# design.net
KiCad netlist of a schematic drawn in Altium Designer
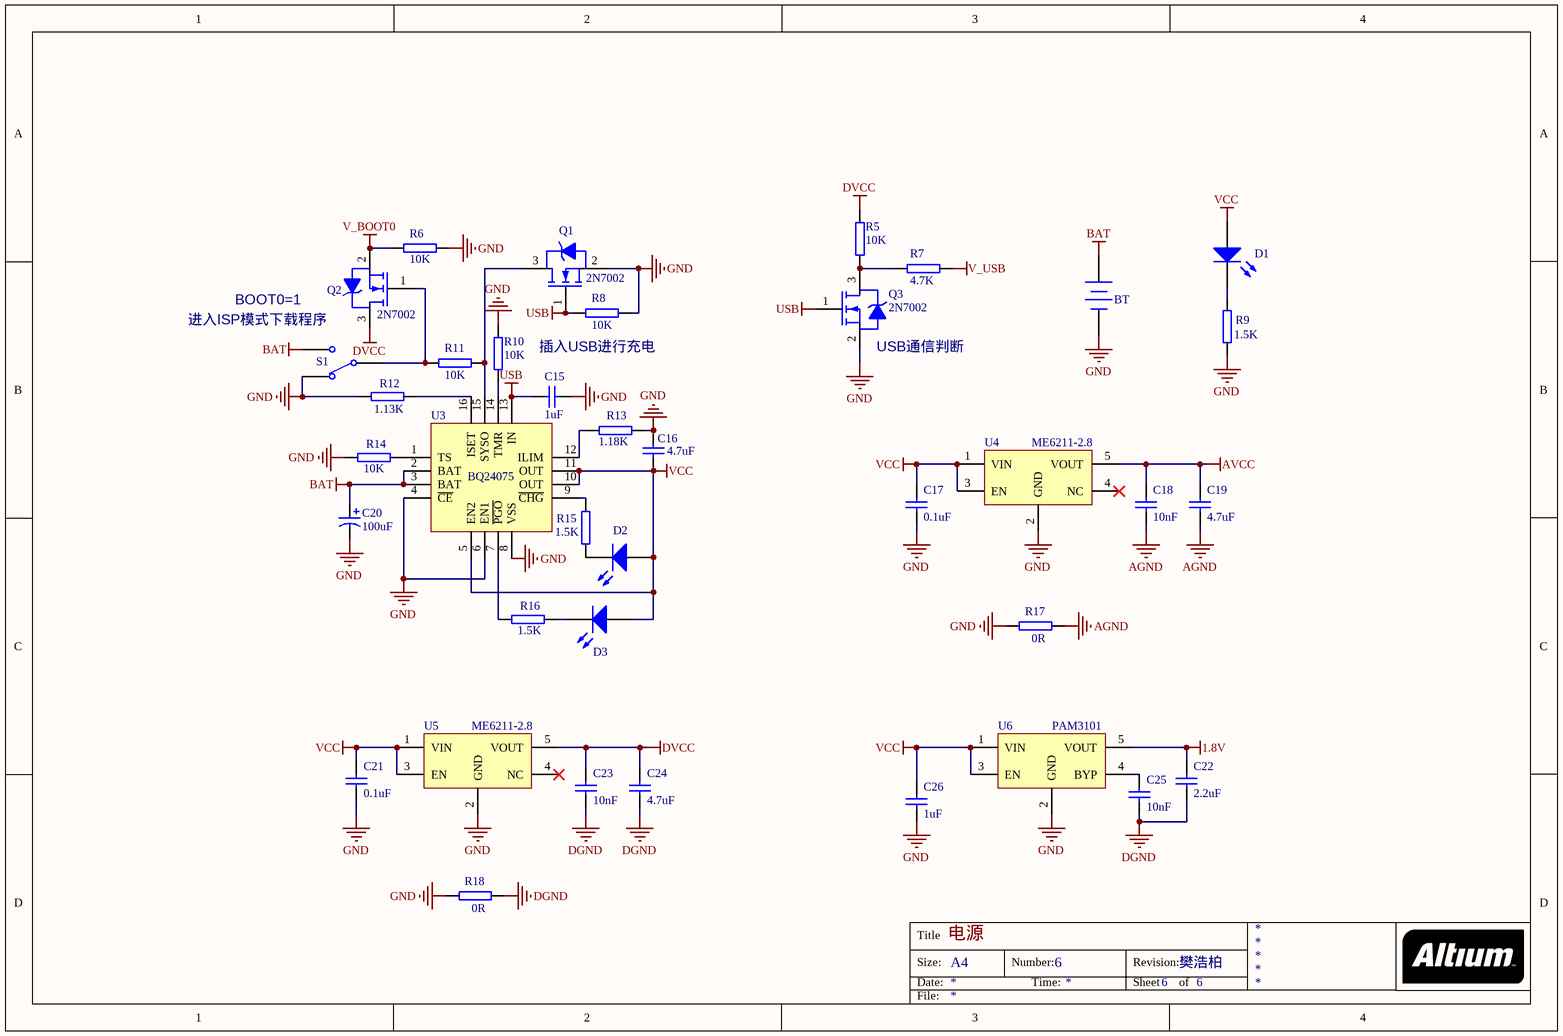
[diagram p0: 电源.SchDoc]

(export (version "E")
  (design (tool "Eeschema 10.0.6"))
  (components
    (comp (ref "BT")
      (value "Battery")
      (footprint "Header-2.0-SMD")
      (libsource (lib "Connectors") (part "Battery"))
    )
    (comp (ref "C15") (value "1uF") (footprint "CAP-0402") (libsource (lib "Connectors") (part "Cap")))
    (comp (ref "C16") (value "4.7uF") (footprint "CAP-0402") (libsource (lib "Connectors") (part "Cap")))
    (comp (ref "C17") (value "0.1uF") (footprint "CAP-0402") (libsource (lib "Connectors") (part "Cap")))
    (comp (ref "C18") (value "10nF") (footprint "CAP-0402") (libsource (lib "Connectors") (part "Cap")))
    (comp (ref "C19") (value "4.7uF") (footprint "CAP-0402") (libsource (lib "Connectors") (part "Cap")))
    (comp (ref "C20")
      (value "100uF")
      (footprint "CASE-A_3216-18")
      (libsource (lib "Connectors") (part "Cap-Pol_1"))
    )
    (comp (ref "C21") (value "0.1uF") (footprint "CAP-0402") (libsource (lib "Connectors") (part "Cap")))
    (comp (ref "C22") (value "2.2uF") (footprint "CAP-0402") (libsource (lib "Connectors") (part "Cap")))
    (comp (ref "C23") (value "10nF") (footprint "CAP-0402") (libsource (lib "Connectors") (part "Cap")))
    (comp (ref "C24") (value "4.7uF") (footprint "CAP-0402") (libsource (lib "Connectors") (part "Cap")))
    (comp (ref "C25") (value "10nF") (footprint "CAP-0402") (libsource (lib "Connectors") (part "Cap")))
    (comp (ref "C26") (value "1uF") (footprint "CAP-0402") (libsource (lib "Connectors") (part "Cap")))
    (comp (ref "D1") (value "LED") (footprint "LED-BLU-0603") (libsource (lib "Connectors") (part "LED")))
    (comp (ref "D2") (value "LED") (footprint "LED-BLU-0603") (libsource (lib "Connectors") (part "LED")))
    (comp (ref "D3") (value "LED") (footprint "LED-RED-0603") (libsource (lib "Connectors") (part "LED")))
    (comp (ref "Q1") (value "2N7002") (footprint "SOT-23-3-L") (libsource (lib "Devices") (part "N-MOS")))
    (comp (ref "Q2") (value "2N7002") (footprint "SOT-23-3-L") (libsource (lib "Devices") (part "N-MOS")))
    (comp (ref "Q3") (value "2N7002") (footprint "SOT-23-3-L") (libsource (lib "Devices") (part "N-MOS")))
    (comp (ref "R5") (value "10K") (footprint "RES-0402") (libsource (lib "Connectors") (part "Res")))
    (comp (ref "R6") (value "10K") (footprint "RES-0402") (libsource (lib "Connectors") (part "Res")))
    (comp (ref "R7") (value "4.7K") (footprint "RES-0402") (libsource (lib "Connectors") (part "Res")))
    (comp (ref "R8") (value "10K") (footprint "RES-0402") (libsource (lib "Connectors") (part "Res")))
    (comp (ref "R9") (value "1.5K") (footprint "RES-0402") (libsource (lib "Connectors") (part "Res")))
    (comp (ref "R10") (value "10K") (footprint "RES-0402") (libsource (lib "Connectors") (part "Res")))
    (comp (ref "R11") (value "10K") (footprint "RES-0402") (libsource (lib "Connectors") (part "Res")))
    (comp (ref "R12") (value "1.13K") (footprint "RES-0402") (libsource (lib "Connectors") (part "Res")))
    (comp (ref "R13") (value "1.18K") (footprint "RES-0402") (libsource (lib "Connectors") (part "Res")))
    (comp (ref "R14") (value "10K") (footprint "RES-0402") (libsource (lib "Connectors") (part "Res")))
    (comp (ref "R15") (value "1.5K") (footprint "RES-0402") (libsource (lib "Connectors") (part "Res")))
    (comp (ref "R16") (value "1.5K") (footprint "RES-0402") (libsource (lib "Connectors") (part "Res")))
    (comp (ref "R17") (value "0R") (footprint "RES-0402") (libsource (lib "Connectors") (part "Res")))
    (comp (ref "R18") (value "0R") (footprint "RES-0402") (libsource (lib "Connectors") (part "Res")))
    (comp (ref "S1") (value "Key-3") (footprint "SW-MSK-12C02") (libsource (lib "Connectors") (part "Key-3")))
    (comp (ref "U3")
      (value "BQ24075")
      (footprint "QFN-16-3x3MM")
      (libsource (lib "Devices") (part "BQ24075"))
    )
    (comp (ref "U4")
      (value "ME6211-2.8")
      (footprint "SOT-23-5")
      (fields (field (name "PUBLISHER") "Altium Limited"))
      (libsource (lib "Devices") (part "LDO"))
    )
    (comp (ref "U5")
      (value "ME6211-2.8")
      (footprint "SOT-23-5")
      (fields (field (name "PUBLISHER") "Altium Limited"))
      (libsource (lib "Devices") (part "LDO"))
    )
    (comp (ref "U6") (value "PAM3101") (footprint "SOT-23-5") (libsource (lib "Devices") (part "PAM3101")))
  )
  (nets
    (net (code "1") (name "1.8V") (class "Default")
      (node (ref "C22") (pin "1") (pinfunction "1_1") (pintype "passive"))
      (node (ref "U6") (pin "5") (pinfunction "VOUT_5") (pintype "passive"))
    )
    (net (code "2") (name "AGND") (class "Default")
      (node (ref "C18") (pin "2") (pinfunction "2_2") (pintype "passive"))
      (node (ref "C19") (pin "2") (pinfunction "2_2") (pintype "passive"))
      (node (ref "R17") (pin "1") (pinfunction "1_1") (pintype "passive"))
    )
    (net (code "3") (name "AVCC") (class "Default")
      (node (ref "C18") (pin "1") (pinfunction "1_1") (pintype "passive"))
      (node (ref "C19") (pin "1") (pinfunction "1_1") (pintype "passive"))
      (node (ref "U4") (pin "5") (pinfunction "VOUT_5") (pintype "passive"))
    )
    (net (code "4") (name "BAT") (class "Default")
      (node (ref "BT") (pin "1") (pinfunction "+_1") (pintype "passive"))
      (node (ref "C20") (pin "A") (pinfunction "A_A") (pintype "passive"))
      (node (ref "S1") (pin "1") (pinfunction "1_1") (pintype "passive"))
      (node (ref "U3") (pin "2") (pinfunction "BAT_2") (pintype "passive"))
      (node (ref "U3") (pin "3") (pinfunction "BAT_3") (pintype "passive"))
    )
    (net (code "5") (name "DGND") (class "Default")
      (node (ref "C22") (pin "2") (pinfunction "2_2") (pintype "passive"))
      (node (ref "C23") (pin "2") (pinfunction "2_2") (pintype "passive"))
      (node (ref "C24") (pin "2") (pinfunction "2_2") (pintype "passive"))
      (node (ref "C25") (pin "2") (pinfunction "2_2") (pintype "passive"))
      (node (ref "R18") (pin "1") (pinfunction "1_1") (pintype "passive"))
    )
    (net (code "6") (name "DVCC") (class "Default")
      (node (ref "C23") (pin "1") (pinfunction "1_1") (pintype "passive"))
      (node (ref "C24") (pin "1") (pinfunction "1_1") (pintype "passive"))
      (node (ref "Q2") (pin "3") (pinfunction "D_3") (pintype "passive"))
      (node (ref "R5") (pin "1") (pinfunction "1_1") (pintype "passive"))
      (node (ref "U5") (pin "5") (pinfunction "VOUT_5") (pintype "passive"))
    )
    (net (code "7") (name "GND") (class "Default")
      (node (ref "BT") (pin "2") (pinfunction "-_2") (pintype "passive"))
      (node (ref "C15") (pin "2") (pinfunction "2_2") (pintype "passive"))
      (node (ref "C16") (pin "1") (pinfunction "1_1") (pintype "passive"))
      (node (ref "C17") (pin "2") (pinfunction "2_2") (pintype "passive"))
      (node (ref "C20") (pin "K") (pinfunction "K_K") (pintype "passive"))
      (node (ref "C21") (pin "2") (pinfunction "2_2") (pintype "passive"))
      (node (ref "C26") (pin "2") (pinfunction "2_2") (pintype "passive"))
      (node (ref "Q1") (pin "2") (pinfunction "S_2") (pintype "passive"))
      (node (ref "Q3") (pin "2") (pinfunction "S_2") (pintype "passive"))
      (node (ref "R10") (pin "2") (pinfunction "2_2") (pintype "passive"))
      (node (ref "R12") (pin "1") (pinfunction "1_1") (pintype "passive"))
      (node (ref "R13") (pin "1") (pinfunction "1_1") (pintype "passive"))
      (node (ref "R14") (pin "1") (pinfunction "1_1") (pintype "passive"))
      (node (ref "R17") (pin "2") (pinfunction "2_2") (pintype "passive"))
      (node (ref "R18") (pin "2") (pinfunction "2_2") (pintype "passive"))
      (node (ref "R6") (pin "1") (pinfunction "1_1") (pintype "passive"))
      (node (ref "R8") (pin "1") (pinfunction "1_1") (pintype "passive"))
      (node (ref "R9") (pin "1") (pinfunction "1_1") (pintype "passive"))
      (node (ref "S1") (pin "3") (pinfunction "3_3") (pintype "passive"))
      (node (ref "U3") (pin "4") (pinfunction "~{CE}_4") (pintype "passive"))
      (node (ref "U3") (pin "6") (pinfunction "EN1_6") (pintype "passive"))
      (node (ref "U3") (pin "8") (pinfunction "VSS_8") (pintype "passive"))
      (node (ref "U4") (pin "2") (pinfunction "GND_2") (pintype "passive"))
      (node (ref "U5") (pin "2") (pinfunction "GND_2") (pintype "passive"))
      (node (ref "U6") (pin "2") (pinfunction "GND_2") (pintype "passive"))
    )
    (net (code "8") (name "Net-(D1-2)") (class "Default")
      (node (ref "D1") (pin "K") (pinfunction "2_K") (pintype "passive"))
      (node (ref "R9") (pin "2") (pinfunction "2_2") (pintype "passive"))
    )
    (net (code "9") (name "Net-(D2-2)") (class "Default")
      (node (ref "D2") (pin "K") (pinfunction "2_K") (pintype "passive"))
      (node (ref "R15") (pin "1") (pinfunction "1_1") (pintype "passive"))
    )
    (net (code "10") (name "Net-(D3-2)") (class "Default")
      (node (ref "D3") (pin "K") (pinfunction "2_K") (pintype "passive"))
      (node (ref "R16") (pin "2") (pinfunction "2_2") (pintype "passive"))
    )
    (net (code "11") (name "Net-(Q1-D)") (class "Default")
      (node (ref "Q1") (pin "3") (pinfunction "D_3") (pintype "passive"))
      (node (ref "R11") (pin "1") (pinfunction "1_1") (pintype "passive"))
      (node (ref "U3") (pin "15") (pinfunction "SYSO_15") (pintype "passive"))
    )
    (net (code "12") (name "Net-(Q2-G)") (class "Default")
      (node (ref "Q2") (pin "1") (pinfunction "G_1") (pintype "passive"))
      (node (ref "R11") (pin "2") (pinfunction "2_2") (pintype "passive"))
      (node (ref "S1") (pin "2") (pinfunction "2_2") (pintype "passive"))
    )
    (net (code "13") (name "Net-(Q3-D)") (class "Default")
      (node (ref "Q3") (pin "3") (pinfunction "D_3") (pintype "passive"))
      (node (ref "R5") (pin "2") (pinfunction "2_2") (pintype "passive"))
      (node (ref "R7") (pin "1") (pinfunction "1_1") (pintype "passive"))
    )
    (net (code "14") (name "Net-(U3-ILIM)") (class "Default")
      (node (ref "R13") (pin "2") (pinfunction "2_2") (pintype "passive"))
      (node (ref "U3") (pin "12") (pinfunction "ILIM_12") (pintype "passive"))
    )
    (net (code "15") (name "Net-(U3-ISET)") (class "Default")
      (node (ref "R12") (pin "2") (pinfunction "2_2") (pintype "passive"))
      (node (ref "U3") (pin "16") (pinfunction "ISET_16") (pintype "passive"))
    )
    (net (code "16") (name "Net-(U3-TMR)") (class "Default")
      (node (ref "R10") (pin "1") (pinfunction "1_1") (pintype "passive"))
      (node (ref "U3") (pin "14") (pinfunction "TMR_14") (pintype "passive"))
    )
    (net (code "17") (name "Net-(U3-TS)") (class "Default")
      (node (ref "R14") (pin "2") (pinfunction "2_2") (pintype "passive"))
      (node (ref "U3") (pin "1") (pinfunction "TS_1") (pintype "passive"))
    )
    (net (code "18") (name "Net-(U3-~{CHG})") (class "Default")
      (node (ref "R15") (pin "2") (pinfunction "2_2") (pintype "passive"))
      (node (ref "U3") (pin "9") (pinfunction "~{CHG}_9") (pintype "passive"))
    )
    (net (code "19") (name "Net-(U3-~{PGO})") (class "Default")
      (node (ref "R16") (pin "1") (pinfunction "1_1") (pintype "passive"))
      (node (ref "U3") (pin "7") (pinfunction "~{PGO}_7") (pintype "passive"))
    )
    (net (code "20") (name "Net-(U6-BYP)") (class "Default")
      (node (ref "C25") (pin "1") (pinfunction "1_1") (pintype "passive"))
      (node (ref "U6") (pin "4") (pinfunction "BYP_4") (pintype "passive"))
    )
    (net (code "21") (name "USB") (class "Default")
      (node (ref "C15") (pin "1") (pinfunction "1_1") (pintype "passive"))
      (node (ref "Q1") (pin "1") (pinfunction "G_1") (pintype "passive"))
      (node (ref "Q3") (pin "1") (pinfunction "G_1") (pintype "passive"))
      (node (ref "R8") (pin "2") (pinfunction "2_2") (pintype "passive"))
      (node (ref "U3") (pin "13") (pinfunction "IN_13") (pintype "passive"))
    )
    (net (code "22") (name "VCC") (class "Default")
      (node (ref "C16") (pin "2") (pinfunction "2_2") (pintype "passive"))
      (node (ref "C17") (pin "1") (pinfunction "1_1") (pintype "passive"))
      (node (ref "C21") (pin "1") (pinfunction "1_1") (pintype "passive"))
      (node (ref "C26") (pin "1") (pinfunction "1_1") (pintype "passive"))
      (node (ref "D1") (pin "A") (pinfunction "1_A") (pintype "passive"))
      (node (ref "D2") (pin "A") (pinfunction "1_A") (pintype "passive"))
      (node (ref "D3") (pin "A") (pinfunction "1_A") (pintype "passive"))
      (node (ref "U3") (pin "10") (pinfunction "OUT_10") (pintype "passive"))
      (node (ref "U3") (pin "11") (pinfunction "OUT_11") (pintype "passive"))
      (node (ref "U3") (pin "5") (pinfunction "EN2_5") (pintype "passive"))
      (node (ref "U4") (pin "1") (pinfunction "VIN_1") (pintype "passive"))
      (node (ref "U4") (pin "3") (pinfunction "EN_3") (pintype "passive"))
      (node (ref "U5") (pin "1") (pinfunction "VIN_1") (pintype "passive"))
      (node (ref "U5") (pin "3") (pinfunction "EN_3") (pintype "passive"))
      (node (ref "U6") (pin "1") (pinfunction "VIN_1") (pintype "passive"))
      (node (ref "U6") (pin "3") (pinfunction "EN_3") (pintype "passive"))
    )
    (net (code "23") (name "V_BOOT0") (class "Default")
      (node (ref "Q2") (pin "2") (pinfunction "S_2") (pintype "passive"))
      (node (ref "R6") (pin "2") (pinfunction "2_2") (pintype "passive"))
    )
    (net (code "24") (name "V_USB") (class "Default")
      (node (ref "R7") (pin "2") (pinfunction "2_2") (pintype "passive"))
    )
    (net (code "25") (name "unconnected-(U4-NC-Pad4)") (class "Default")
      (node (ref "U4") (pin "4") (pinfunction "NC_4") (pintype "passive+no_connect"))
    )
    (net (code "26") (name "unconnected-(U5-NC-Pad4)") (class "Default")
      (node (ref "U5") (pin "4") (pinfunction "NC_4") (pintype "passive+no_connect"))
    )
  )
)
